# TOFSensorBoard.net
KiCad netlist of a schematic drawn in EAGLE
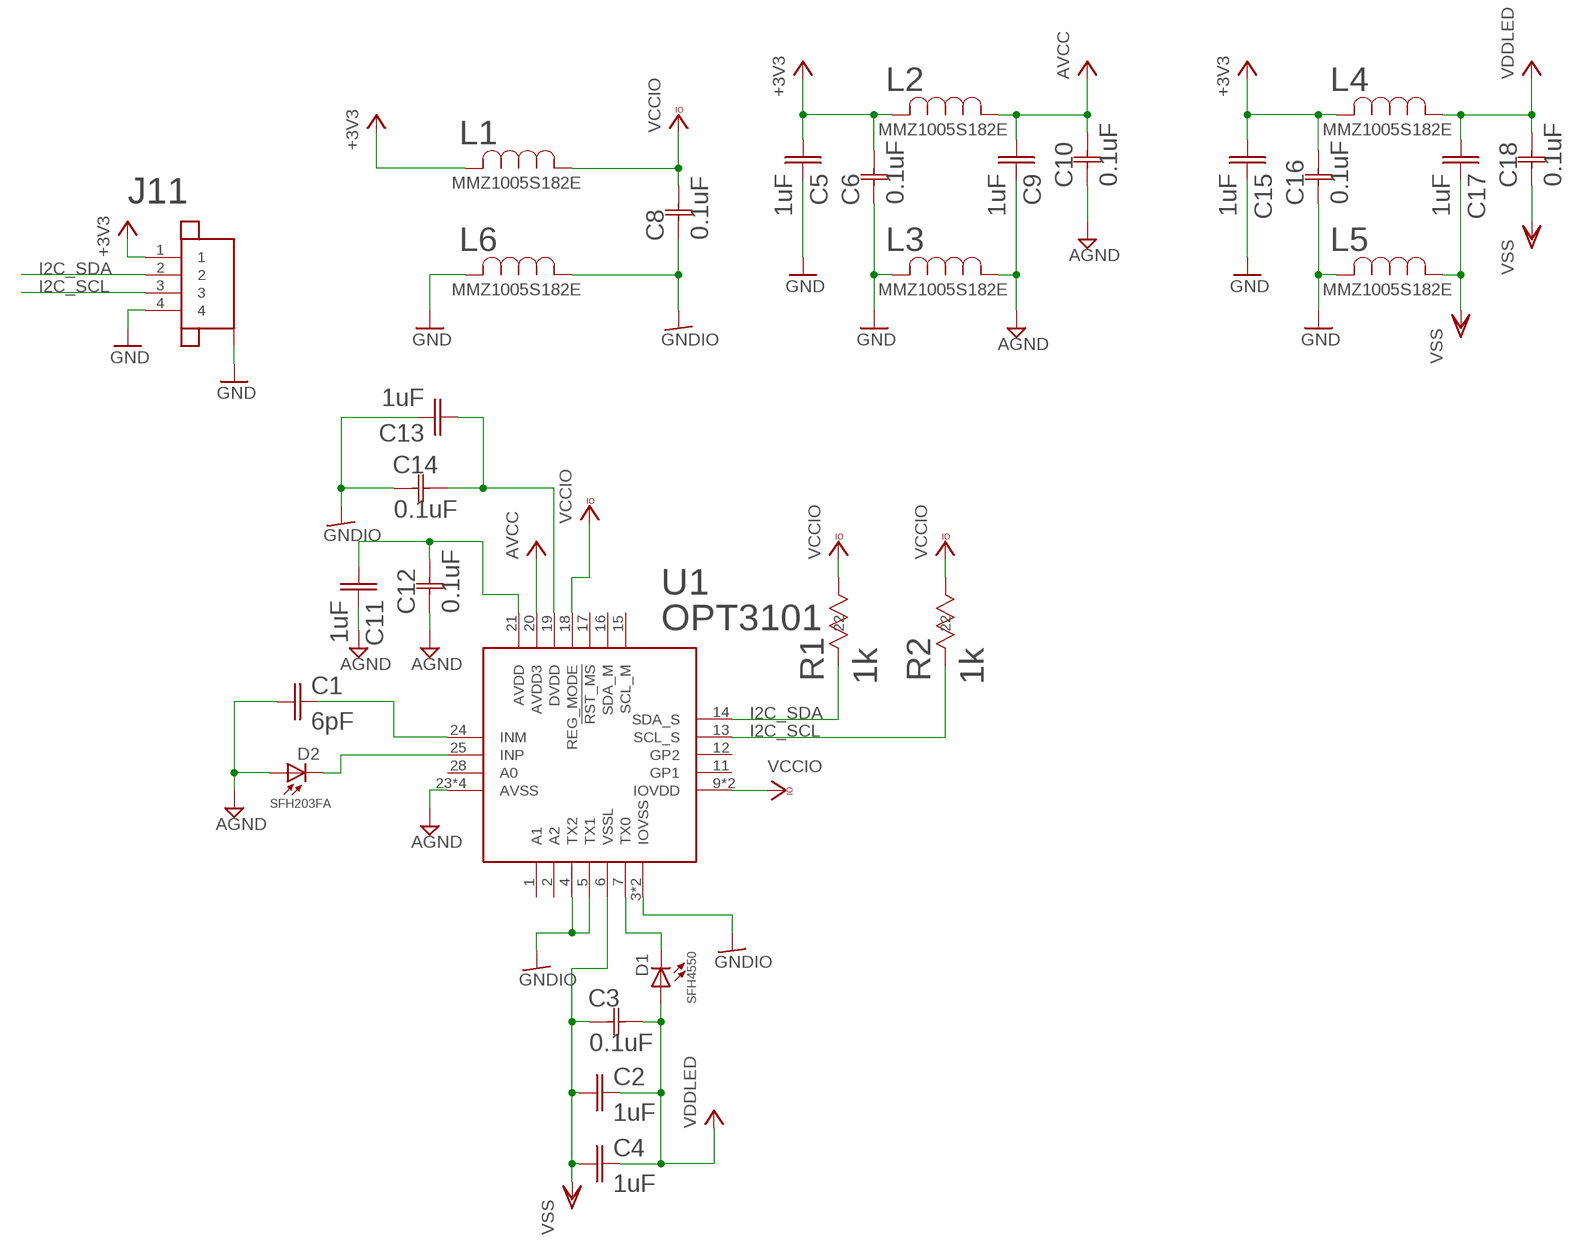
[diagram p0: schematic, sheet 1]

(export (version "E")
  (design (tool "Eeschema 10.0.6"))
  (components
    (comp (ref "C1")
      (value "6pF")
      (footprint "eagle-import:0402_CAPACITOR")
      (libsource (lib "eagle-import") (part "CL05C060DB5NCNC"))
    )
    (comp (ref "C2")
      (value "1uF")
      (footprint "eagle-import:0603_CAPACITOR")
      (libsource (lib "eagle-import") (part "CL10A105KP8NNNC"))
    )
    (comp (ref "C3")
      (value "0.1uF")
      (footprint "eagle-import:0402-M")
      (fields (field (name "MANUFACTURER_PART_NUMBER") "0402ZD104KAT2A"))
      (libsource (lib "eagle-import") (part "0402ZD104KAT2A0402-M"))
    )
    (comp (ref "C4")
      (value "1uF")
      (footprint "eagle-import:0603_CAPACITOR")
      (libsource (lib "eagle-import") (part "CL10A105KP8NNNC"))
    )
    (comp (ref "C5")
      (value "1uF")
      (footprint "eagle-import:0603_CAPACITOR")
      (libsource (lib "eagle-import") (part "CL10A105KP8NNNC"))
    )
    (comp (ref "C6")
      (value "0.1uF")
      (footprint "eagle-import:0402-M")
      (fields (field (name "MANUFACTURER_PART_NUMBER") "0402ZD104KAT2A"))
      (libsource (lib "eagle-import") (part "0402ZD104KAT2A0402-M"))
    )
    (comp (ref "C8")
      (value "0.1uF")
      (footprint "eagle-import:0402-M")
      (fields (field (name "MANUFACTURER_PART_NUMBER") "0402ZD104KAT2A"))
      (libsource (lib "eagle-import") (part "0402ZD104KAT2A0402-M"))
    )
    (comp (ref "C9")
      (value "1uF")
      (footprint "eagle-import:0603_CAPACITOR")
      (libsource (lib "eagle-import") (part "CL10A105KP8NNNC"))
    )
    (comp (ref "C10")
      (value "0.1uF")
      (footprint "eagle-import:0402-M")
      (fields (field (name "MANUFACTURER_PART_NUMBER") "0402ZD104KAT2A"))
      (libsource (lib "eagle-import") (part "0402ZD104KAT2A0402-M"))
    )
    (comp (ref "C11")
      (value "1uF")
      (footprint "eagle-import:0603_CAPACITOR")
      (libsource (lib "eagle-import") (part "CL10A105KP8NNNC"))
    )
    (comp (ref "C12")
      (value "0.1uF")
      (footprint "eagle-import:0402-M")
      (fields (field (name "MANUFACTURER_PART_NUMBER") "0402ZD104KAT2A"))
      (libsource (lib "eagle-import") (part "0402ZD104KAT2A0402-M"))
    )
    (comp (ref "C13")
      (value "1uF")
      (footprint "eagle-import:0603_CAPACITOR")
      (libsource (lib "eagle-import") (part "CL10A105KP8NNNC"))
    )
    (comp (ref "C14")
      (value "0.1uF")
      (footprint "eagle-import:0402-M")
      (fields (field (name "MANUFACTURER_PART_NUMBER") "0402ZD104KAT2A"))
      (libsource (lib "eagle-import") (part "0402ZD104KAT2A0402-M"))
    )
    (comp (ref "C15")
      (value "1uF")
      (footprint "eagle-import:0603_CAPACITOR")
      (libsource (lib "eagle-import") (part "CL10A105KP8NNNC"))
    )
    (comp (ref "C16")
      (value "0.1uF")
      (footprint "eagle-import:0402-M")
      (fields (field (name "MANUFACTURER_PART_NUMBER") "0402ZD104KAT2A"))
      (libsource (lib "eagle-import") (part "0402ZD104KAT2A0402-M"))
    )
    (comp (ref "C17")
      (value "1uF")
      (footprint "eagle-import:0603_CAPACITOR")
      (libsource (lib "eagle-import") (part "CL10A105KP8NNNC"))
    )
    (comp (ref "C18")
      (value "0.1uF")
      (footprint "eagle-import:0402-M")
      (fields (field (name "MANUFACTURER_PART_NUMBER") "0402ZD104KAT2A"))
      (libsource (lib "eagle-import") (part "0402ZD104KAT2A0402-M"))
    )
    (comp (ref "D1")
      (value "SFH4550")
      (footprint "eagle-import:5MM_LED")
      (libsource (lib "eagle-import") (part "SFH4550"))
    )
    (comp (ref "D2")
      (value "SFH203FA")
      (footprint "eagle-import:5MM_LED")
      (libsource (lib "eagle-import") (part "SFH203FA"))
    )
    (comp (ref "J11")
      (value "JST_SH_4POS")
      (footprint "eagle-import:JST_SH_4POS")
      (libsource (lib "eagle-import") (part "JST_SH_4POS"))
    )
    (comp (ref "L1")
      (value "MMZ1005S182ET000IND_1005-M")
      (footprint "eagle-import:IND_1005-M")
      (fields (field (name "MANUFACTURER_PART_NUMBER") "MMZ1005S182ET000"))
      (libsource (lib "eagle-import") (part "MMZ1005S182ET000IND_1005-M"))
    )
    (comp (ref "L2")
      (value "MMZ1005S182ET000IND_1005-M")
      (footprint "eagle-import:IND_1005-M")
      (fields (field (name "MANUFACTURER_PART_NUMBER") "MMZ1005S182ET000"))
      (libsource (lib "eagle-import") (part "MMZ1005S182ET000IND_1005-M"))
    )
    (comp (ref "L3")
      (value "MMZ1005S182ET000IND_1005-M")
      (footprint "eagle-import:IND_1005-M")
      (fields (field (name "MANUFACTURER_PART_NUMBER") "MMZ1005S182ET000"))
      (libsource (lib "eagle-import") (part "MMZ1005S182ET000IND_1005-M"))
    )
    (comp (ref "L4")
      (value "MMZ1005S182ET000IND_1005-M")
      (footprint "eagle-import:IND_1005-M")
      (fields (field (name "MANUFACTURER_PART_NUMBER") "MMZ1005S182ET000"))
      (libsource (lib "eagle-import") (part "MMZ1005S182ET000IND_1005-M"))
    )
    (comp (ref "L5")
      (value "MMZ1005S182ET000IND_1005-M")
      (footprint "eagle-import:IND_1005-M")
      (fields (field (name "MANUFACTURER_PART_NUMBER") "MMZ1005S182ET000"))
      (libsource (lib "eagle-import") (part "MMZ1005S182ET000IND_1005-M"))
    )
    (comp (ref "L6")
      (value "MMZ1005S182ET000IND_1005-M")
      (footprint "eagle-import:IND_1005-M")
      (fields (field (name "MANUFACTURER_PART_NUMBER") "MMZ1005S182ET000"))
      (libsource (lib "eagle-import") (part "MMZ1005S182ET000IND_1005-M"))
    )
    (comp (ref "R1")
      (value "1k")
      (footprint "eagle-import:RC0603N-M")
      (fields
        (field (name "DIGIKEYPARTNUMBER") "3111.0KGRTRND")
        (field (name "MANUFACTURER_PART_NUMBER") "RC0603JR071KL")
        (field (name "NEWARKPARTNUMBER") "14M7231")
        (field (name "COPYRIGHT") "Copyright C 2015 Accelerated Designs. All rights reserved")
      )
      (libsource (lib "eagle-import") (part "RC0603JR-071KLRC0603N-M"))
    )
    (comp (ref "R2")
      (value "1k")
      (footprint "eagle-import:RC0603N-M")
      (fields
        (field (name "DIGIKEYPARTNUMBER") "3111.0KGRTRND")
        (field (name "MANUFACTURER_PART_NUMBER") "RC0603JR071KL")
        (field (name "NEWARKPARTNUMBER") "14M7231")
        (field (name "COPYRIGHT") "Copyright C 2015 Accelerated Designs. All rights reserved")
      )
      (libsource (lib "eagle-import") (part "RC0603JR-071KLRC0603N-M"))
    )
    (comp (ref "U1")
      (value "OPT3101")
      (footprint "eagle-import:28-VQFN")
      (libsource (lib "eagle-import") (part "OPT3101"))
    )
  )
  (nets
    (net (code "1") (name "+3V3") (class "Default")
      (node (ref "C15") (pin "1") (pinfunction "1_1") (pintype "bidirectional"))
      (node (ref "C16") (pin "2") (pinfunction "2_2") (pintype "passive"))
      (node (ref "C5") (pin "1") (pinfunction "1_1") (pintype "bidirectional"))
      (node (ref "C6") (pin "2") (pinfunction "2_2") (pintype "passive"))
      (node (ref "J11") (pin "1") (pinfunction "1_1") (pintype "bidirectional"))
      (node (ref "L1") (pin "2") (pinfunction "2_2") (pintype "passive"))
      (node (ref "L2") (pin "2") (pinfunction "2_2") (pintype "passive"))
      (node (ref "L4") (pin "2") (pinfunction "2_2") (pintype "passive"))
    )
    (net (code "2") (name "/I2C_SCL") (class "Default")
      (node (ref "J11") (pin "3") (pinfunction "3_3") (pintype "bidirectional"))
      (node (ref "R2") (pin "2") (pinfunction "22_2") (pintype "passive"))
      (node (ref "U1") (pin "13") (pinfunction "SCL_S_13") (pintype "bidirectional"))
    )
    (net (code "3") (name "/I2C_SDA") (class "Default")
      (node (ref "J11") (pin "2") (pinfunction "2_2") (pintype "bidirectional"))
      (node (ref "R1") (pin "2") (pinfunction "22_2") (pintype "passive"))
      (node (ref "U1") (pin "14") (pinfunction "SDA_S_14") (pintype "bidirectional"))
    )
    (net (code "4") (name "AGND") (class "Default")
      (node (ref "C1") (pin "1") (pinfunction "1_1") (pintype "bidirectional"))
      (node (ref "C10") (pin "1") (pinfunction "1_1") (pintype "passive"))
      (node (ref "C11") (pin "2") (pinfunction "2_2") (pintype "bidirectional"))
      (node (ref "C12") (pin "1") (pinfunction "1_1") (pintype "passive"))
      (node (ref "C9") (pin "2") (pinfunction "2_2") (pintype "bidirectional"))
      (node (ref "D2") (pin "A") (pinfunction "A_A") (pintype "passive"))
      (node (ref "L3") (pin "1") (pinfunction "1_1") (pintype "passive"))
      (node (ref "U1") (pin "23") (pinfunction "AVSS_23") (pintype "bidirectional"))
      (node (ref "U1") (pin "26") (pinfunction "AVSS_26") (pintype "bidirectional"))
      (node (ref "U1") (pin "27") (pinfunction "AVSS_27") (pintype "bidirectional"))
      (node (ref "U1") (pin "29") (pinfunction "AVSS_29") (pintype "bidirectional"))
    )
    (net (code "5") (name "AVCC") (class "Default")
      (node (ref "C10") (pin "2") (pinfunction "2_2") (pintype "passive"))
      (node (ref "C9") (pin "1") (pinfunction "1_1") (pintype "bidirectional"))
      (node (ref "L2") (pin "1") (pinfunction "1_1") (pintype "passive"))
      (node (ref "U1") (pin "20") (pinfunction "AVDD3_20") (pintype "bidirectional"))
    )
    (net (code "6") (name "GND") (class "Default")
      (node (ref "C15") (pin "2") (pinfunction "2_2") (pintype "bidirectional"))
      (node (ref "C16") (pin "1") (pinfunction "1_1") (pintype "passive"))
      (node (ref "C5") (pin "2") (pinfunction "2_2") (pintype "bidirectional"))
      (node (ref "C6") (pin "1") (pinfunction "1_1") (pintype "passive"))
      (node (ref "J11") (pin "4") (pinfunction "4_4") (pintype "bidirectional"))
      (node (ref "J11") (pin "P$5") (pinfunction "5_P$5") (pintype "bidirectional"))
      (node (ref "J11") (pin "P$6") (pinfunction "5_P$6") (pintype "bidirectional"))
      (node (ref "L3") (pin "2") (pinfunction "2_2") (pintype "passive"))
      (node (ref "L5") (pin "2") (pinfunction "2_2") (pintype "passive"))
      (node (ref "L6") (pin "2") (pinfunction "2_2") (pintype "passive"))
    )
    (net (code "7") (name "GNDIO") (class "Default")
      (node (ref "C13") (pin "2") (pinfunction "2_2") (pintype "bidirectional"))
      (node (ref "C14") (pin "1") (pinfunction "1_1") (pintype "passive"))
      (node (ref "C8") (pin "1") (pinfunction "1_1") (pintype "passive"))
      (node (ref "L6") (pin "1") (pinfunction "1_1") (pintype "passive"))
      (node (ref "U1") (pin "3") (pinfunction "IOVSS_3") (pintype "bidirectional"))
      (node (ref "U1") (pin "4") (pinfunction "TX2_4") (pintype "bidirectional"))
      (node (ref "U1") (pin "5") (pinfunction "TX1_5") (pintype "bidirectional"))
      (node (ref "U1") (pin "8") (pinfunction "IOVSS_8") (pintype "bidirectional"))
    )
    (net (code "8") (name "Net-(U1-AVDD)") (class "Default")
      (node (ref "C11") (pin "1") (pinfunction "1_1") (pintype "bidirectional"))
      (node (ref "C12") (pin "2") (pinfunction "2_2") (pintype "passive"))
      (node (ref "U1") (pin "21") (pinfunction "AVDD_21") (pintype "bidirectional"))
    )
    (net (code "9") (name "Net-(U1-DVDD)") (class "Default")
      (node (ref "C13") (pin "1") (pinfunction "1_1") (pintype "bidirectional"))
      (node (ref "C14") (pin "2") (pinfunction "2_2") (pintype "passive"))
      (node (ref "U1") (pin "19") (pinfunction "DVDD_19") (pintype "bidirectional"))
    )
    (net (code "10") (name "Net-(U1-INM)") (class "Default")
      (node (ref "C1") (pin "2") (pinfunction "2_2") (pintype "bidirectional"))
      (node (ref "U1") (pin "24") (pinfunction "INM_24") (pintype "bidirectional"))
    )
    (net (code "11") (name "Net-(U1-INP)") (class "Default")
      (node (ref "D2") (pin "C") (pinfunction "C_C") (pintype "passive"))
      (node (ref "U1") (pin "25") (pinfunction "INP_25") (pintype "bidirectional"))
    )
    (net (code "12") (name "Net-(U1-TX0)") (class "Default")
      (node (ref "D1") (pin "C") (pinfunction "C_C") (pintype "passive"))
      (node (ref "U1") (pin "7") (pinfunction "TX0_7") (pintype "bidirectional"))
    )
    (net (code "13") (name "VCCIO") (class "Default")
      (node (ref "C8") (pin "2") (pinfunction "2_2") (pintype "passive"))
      (node (ref "L1") (pin "1") (pinfunction "1_1") (pintype "passive"))
      (node (ref "R1") (pin "1") (pinfunction "11_1") (pintype "passive"))
      (node (ref "R2") (pin "1") (pinfunction "11_1") (pintype "passive"))
      (node (ref "U1") (pin "10") (pinfunction "IOVDD_10") (pintype "bidirectional"))
      (node (ref "U1") (pin "18") (pinfunction "REG_MODE_18") (pintype "bidirectional"))
      (node (ref "U1") (pin "9") (pinfunction "IOVDD_9") (pintype "bidirectional"))
    )
    (net (code "14") (name "VDDLED") (class "Default")
      (node (ref "C17") (pin "1") (pinfunction "1_1") (pintype "bidirectional"))
      (node (ref "C18") (pin "2") (pinfunction "2_2") (pintype "passive"))
      (node (ref "C2") (pin "2") (pinfunction "2_2") (pintype "bidirectional"))
      (node (ref "C3") (pin "2") (pinfunction "2_2") (pintype "passive"))
      (node (ref "C4") (pin "2") (pinfunction "2_2") (pintype "bidirectional"))
      (node (ref "D1") (pin "A") (pinfunction "A_A") (pintype "passive"))
      (node (ref "L4") (pin "1") (pinfunction "1_1") (pintype "passive"))
    )
    (net (code "15") (name "VSS") (class "Default")
      (node (ref "C17") (pin "2") (pinfunction "2_2") (pintype "bidirectional"))
      (node (ref "C18") (pin "1") (pinfunction "1_1") (pintype "passive"))
      (node (ref "C2") (pin "1") (pinfunction "1_1") (pintype "bidirectional"))
      (node (ref "C3") (pin "1") (pinfunction "1_1") (pintype "passive"))
      (node (ref "C4") (pin "1") (pinfunction "1_1") (pintype "bidirectional"))
      (node (ref "L5") (pin "1") (pinfunction "1_1") (pintype "passive"))
      (node (ref "U1") (pin "6") (pinfunction "VSSL_6") (pintype "bidirectional"))
    )
    (net (code "16") (name "unconnected-(U1-A0-Pad28)") (class "Default")
      (node (ref "U1") (pin "28") (pinfunction "A0_28") (pintype "bidirectional"))
    )
    (net (code "17") (name "unconnected-(U1-A1-Pad1)") (class "Default")
      (node (ref "U1") (pin "1") (pinfunction "A1_1") (pintype "bidirectional"))
    )
    (net (code "18") (name "unconnected-(U1-A2-Pad2)") (class "Default")
      (node (ref "U1") (pin "2") (pinfunction "A2_2") (pintype "bidirectional"))
    )
    (net (code "19") (name "unconnected-(U1-GP1-Pad11)") (class "Default")
      (node (ref "U1") (pin "11") (pinfunction "GP1_11") (pintype "bidirectional"))
    )
    (net (code "20") (name "unconnected-(U1-GP2-Pad12)") (class "Default")
      (node (ref "U1") (pin "12") (pinfunction "GP2_12") (pintype "bidirectional"))
    )
    (net (code "21") (name "unconnected-(U1-SCL_M-Pad15)") (class "Default")
      (node (ref "U1") (pin "15") (pinfunction "SCL_M_15") (pintype "bidirectional"))
    )
    (net (code "22") (name "unconnected-(U1-SDA_M-Pad16)") (class "Default")
      (node (ref "U1") (pin "16") (pinfunction "SDA_M_16") (pintype "bidirectional"))
    )
    (net (code "23") (name "unconnected-(U1-~{RST_MS}-Pad17)") (class "Default")
      (node (ref "U1") (pin "17") (pinfunction "~{RST_MS}_17") (pintype "bidirectional"))
    )
  )
)
